# main_328p.net
KiCad netlist of a schematic drawn in EAGLE
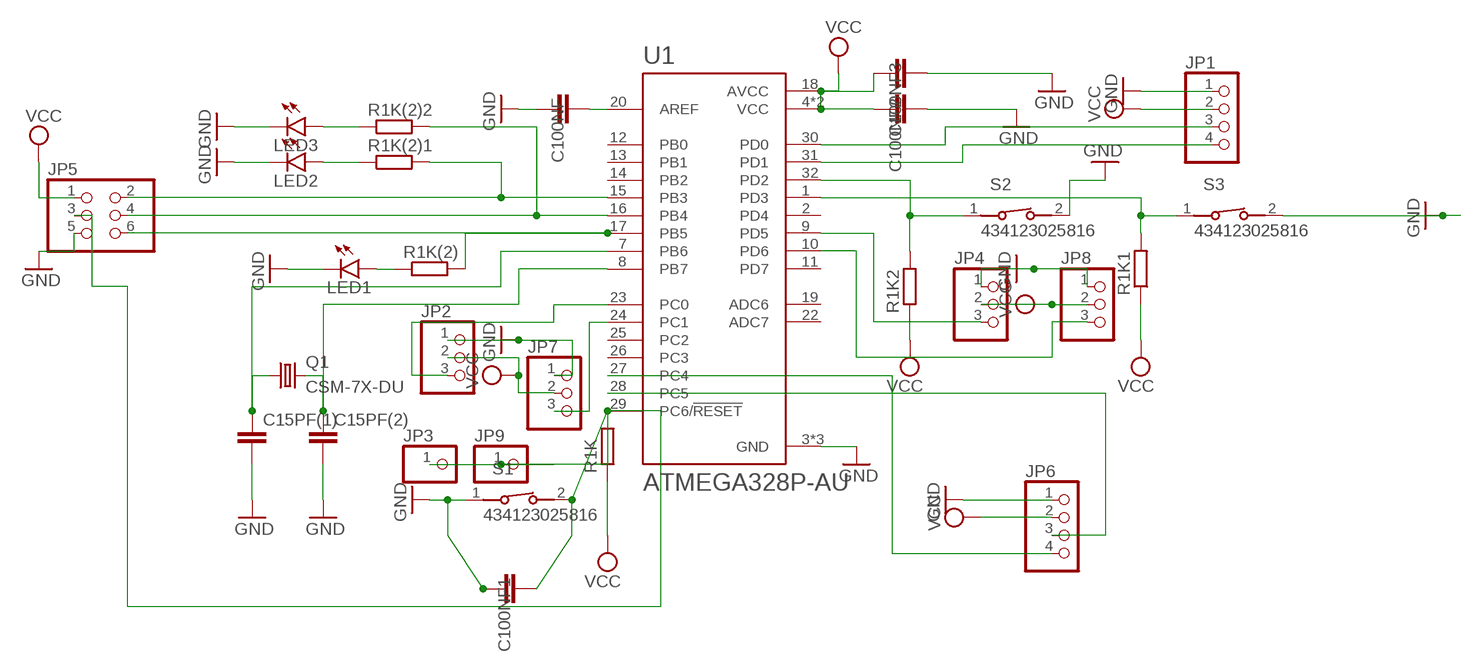
[diagram p0: schematic, sheet 1]

(export (version "E")
  (design (tool "Eeschema 10.0.6"))
  (components
    (comp (ref "C15PF(1)")
      (value "C-EUC0603")
      (footprint "eagle-import:C0603")
      (libsource (lib "eagle-import") (part "C-EUC0603"))
    )
    (comp (ref "C15PF(2)")
      (value "C-EUC0603")
      (footprint "eagle-import:C0603")
      (libsource (lib "eagle-import") (part "C-EUC0603"))
    )
    (comp (ref "C100NF")
      (value "C-EUC0603")
      (footprint "eagle-import:C0603")
      (libsource (lib "eagle-import") (part "C-EUC0603"))
    )
    (comp (ref "C100NF1")
      (value "C-EUC0603")
      (footprint "eagle-import:C0603")
      (libsource (lib "eagle-import") (part "C-EUC0603"))
    )
    (comp (ref "C100NF2")
      (value "C-EUC0603")
      (footprint "eagle-import:C0603")
      (libsource (lib "eagle-import") (part "C-EUC0603"))
    )
    (comp (ref "C100NF3")
      (value "C-EUC0603")
      (footprint "eagle-import:C0603")
      (libsource (lib "eagle-import") (part "C-EUC0603"))
    )
    (comp (ref "JP1")
      (value "PINHD-1X04_2.54-SMD")
      (footprint "eagle-import:1X04SMD")
      (libsource (lib "eagle-import") (part "PINHD-1X04_2.54-SMD"))
    )
    (comp (ref "JP2")
      (value "PINHD-1X03_2.54-SMD")
      (footprint "eagle-import:1X03SMD")
      (libsource (lib "eagle-import") (part "PINHD-1X03_2.54-SMD"))
    )
    (comp (ref "JP3")
      (value "PINHD-1X01_2.54")
      (footprint "eagle-import:1X01")
      (libsource (lib "eagle-import") (part "PINHD-1X01_2.54"))
    )
    (comp (ref "JP4")
      (value "PINHD-1X03_2.54-SMD")
      (footprint "eagle-import:1X03SMD")
      (libsource (lib "eagle-import") (part "PINHD-1X03_2.54-SMD"))
    )
    (comp (ref "JP5")
      (value "PINHD-2X03_2.54-SMD")
      (footprint "eagle-import:2X03SMD")
      (libsource (lib "eagle-import") (part "PINHD-2X03_2.54-SMD"))
    )
    (comp (ref "JP6")
      (value "PINHD-1X04_2.54-SMD")
      (footprint "eagle-import:1X04SMD")
      (libsource (lib "eagle-import") (part "PINHD-1X04_2.54-SMD"))
    )
    (comp (ref "JP7")
      (value "PINHD-1X03_2.54-SMD")
      (footprint "eagle-import:1X03SMD")
      (libsource (lib "eagle-import") (part "PINHD-1X03_2.54-SMD"))
    )
    (comp (ref "JP8")
      (value "PINHD-1X03_2.54-SMD")
      (footprint "eagle-import:1X03SMD")
      (libsource (lib "eagle-import") (part "PINHD-1X03_2.54-SMD"))
    )
    (comp (ref "JP9")
      (value "PINHD-1X01_2.54")
      (footprint "eagle-import:1X01")
      (libsource (lib "eagle-import") (part "PINHD-1X01_2.54"))
    )
    (comp (ref "LED1")
      (value "LEDCHIPLED_1206")
      (footprint "eagle-import:CHIPLED_1206")
      (libsource (lib "eagle-import") (part "LEDCHIPLED_1206"))
    )
    (comp (ref "LED2")
      (value "LEDCHIPLED_1206")
      (footprint "eagle-import:CHIPLED_1206")
      (libsource (lib "eagle-import") (part "LEDCHIPLED_1206"))
    )
    (comp (ref "LED3")
      (value "LEDCHIPLED_1206")
      (footprint "eagle-import:CHIPLED_1206")
      (libsource (lib "eagle-import") (part "LEDCHIPLED_1206"))
    )
    (comp (ref "Q1")
      (value "CSM-7X-DU")
      (footprint "eagle-import:CSM-7X-DU")
      (libsource (lib "eagle-import") (part "CSM-7X-DU"))
    )
    (comp (ref "R1K")
      (value "R-EU_R1206")
      (footprint "eagle-import:R1206")
      (libsource (lib "eagle-import") (part "R-EU_R1206"))
    )
    (comp (ref "R1K(2)")
      (value "R-EU_R1206")
      (footprint "eagle-import:R1206")
      (libsource (lib "eagle-import") (part "R-EU_R1206"))
    )
    (comp (ref "R1K(2)1")
      (value "R-EU_R1206")
      (footprint "eagle-import:R1206")
      (libsource (lib "eagle-import") (part "R-EU_R1206"))
    )
    (comp (ref "R1K(2)2")
      (value "R-EU_R1206")
      (footprint "eagle-import:R1206")
      (libsource (lib "eagle-import") (part "R-EU_R1206"))
    )
    (comp (ref "R1K1")
      (value "R-EU_R1206")
      (footprint "eagle-import:R1206")
      (libsource (lib "eagle-import") (part "R-EU_R1206"))
    )
    (comp (ref "R1K2")
      (value "R-EU_R1206")
      (footprint "eagle-import:R1206")
      (libsource (lib "eagle-import") (part "R-EU_R1206"))
    )
    (comp (ref "S1")
      (value "434123025816")
      (footprint "eagle-import:434123025816")
      (fields (field (name "MF") "Wurth Electronics"))
      (libsource (lib "eagle-import") (part "434123025816"))
    )
    (comp (ref "S2")
      (value "434123025816")
      (footprint "eagle-import:434123025816")
      (fields (field (name "MF") "Wurth Electronics"))
      (libsource (lib "eagle-import") (part "434123025816"))
    )
    (comp (ref "S3")
      (value "434123025816")
      (footprint "eagle-import:434123025816")
      (fields (field (name "MF") "Wurth Electronics"))
      (libsource (lib "eagle-import") (part "434123025816"))
    )
    (comp (ref "U1")
      (value "ATMEGA328P-AU")
      (footprint "eagle-import:QFP80P900X900X120-32N")
      (fields (field (name "MF") "Microchip Technology"))
      (libsource (lib "eagle-import") (part "ATMEGA328P-AU"))
    )
  )
  (nets
    (net (code "1") (name "GND") (class "Default")
      (node (ref "C100NF") (pin "1") (pinfunction "1_1") (pintype "passive"))
      (node (ref "C100NF1") (pin "1") (pinfunction "1_1") (pintype "passive"))
      (node (ref "C100NF2") (pin "2") (pinfunction "2_2") (pintype "passive"))
      (node (ref "C100NF3") (pin "2") (pinfunction "2_2") (pintype "passive"))
      (node (ref "C15PF(1)") (pin "2") (pinfunction "2_2") (pintype "passive"))
      (node (ref "C15PF(2)") (pin "2") (pinfunction "2_2") (pintype "passive"))
      (node (ref "JP1") (pin "1") (pinfunction "1_1") (pintype "passive"))
      (node (ref "JP2") (pin "1") (pinfunction "1_1") (pintype "passive"))
      (node (ref "JP4") (pin "1") (pinfunction "1_1") (pintype "passive"))
      (node (ref "JP5") (pin "5") (pinfunction "5_5") (pintype "passive"))
      (node (ref "JP6") (pin "1") (pinfunction "1_1") (pintype "passive"))
      (node (ref "JP7") (pin "1") (pinfunction "1_1") (pintype "passive"))
      (node (ref "JP8") (pin "1") (pinfunction "1_1") (pintype "passive"))
      (node (ref "LED1") (pin "C") (pinfunction "C_C") (pintype "passive"))
      (node (ref "LED2") (pin "C") (pinfunction "C_C") (pintype "passive"))
      (node (ref "LED3") (pin "C") (pinfunction "C_C") (pintype "passive"))
      (node (ref "S1") (pin "1") (pinfunction "1_1") (pintype "passive"))
      (node (ref "S2") (pin "2") (pinfunction "2_2") (pintype "passive"))
      (node (ref "S3") (pin "2") (pinfunction "2_2") (pintype "passive"))
      (node (ref "U1") (pin "21") (pinfunction "GND_21") (pintype "power_in"))
      (node (ref "U1") (pin "3") (pinfunction "GND_3") (pintype "power_in"))
      (node (ref "U1") (pin "5") (pinfunction "GND_5") (pintype "power_in"))
    )
    (net (code "2") (name "Net-(LED1-PadA)") (class "Default")
      (node (ref "LED1") (pin "A") (pinfunction "A_A") (pintype "passive"))
      (node (ref "R1K(2)") (pin "1") (pinfunction "1_1") (pintype "passive"))
    )
    (net (code "3") (name "Net-(LED2-PadA)") (class "Default")
      (node (ref "LED2") (pin "A") (pinfunction "A_A") (pintype "passive"))
      (node (ref "R1K(2)1") (pin "1") (pinfunction "1_1") (pintype "passive"))
    )
    (net (code "4") (name "Net-(LED3-PadA)") (class "Default")
      (node (ref "LED3") (pin "A") (pinfunction "A_A") (pintype "passive"))
      (node (ref "R1K(2)2") (pin "1") (pinfunction "1_1") (pintype "passive"))
    )
    (net (code "5") (name "Net-(U1-AREF)") (class "Default")
      (node (ref "C100NF") (pin "2") (pinfunction "2_2") (pintype "passive"))
      (node (ref "U1") (pin "20") (pinfunction "AREF_20") (pintype "input"))
    )
    (net (code "6") (name "Net-(U1-PB3)") (class "Default")
      (node (ref "JP5") (pin "2") (pinfunction "2_2") (pintype "passive"))
      (node (ref "R1K(2)1") (pin "2") (pinfunction "2_2") (pintype "passive"))
      (node (ref "U1") (pin "15") (pinfunction "PB3_15") (pintype "bidirectional"))
    )
    (net (code "7") (name "Net-(U1-PB4)") (class "Default")
      (node (ref "JP5") (pin "4") (pinfunction "4_4") (pintype "passive"))
      (node (ref "R1K(2)2") (pin "2") (pinfunction "2_2") (pintype "passive"))
      (node (ref "U1") (pin "16") (pinfunction "PB4_16") (pintype "bidirectional"))
    )
    (net (code "8") (name "Net-(U1-PB5)") (class "Default")
      (node (ref "JP5") (pin "6") (pinfunction "6_6") (pintype "passive"))
      (node (ref "R1K(2)") (pin "2") (pinfunction "2_2") (pintype "passive"))
      (node (ref "U1") (pin "17") (pinfunction "PB5_17") (pintype "bidirectional"))
    )
    (net (code "9") (name "Net-(U1-PB6)") (class "Default")
      (node (ref "C15PF(1)") (pin "1") (pinfunction "1_1") (pintype "passive"))
      (node (ref "Q1") (pin "1") (pinfunction "1_1") (pintype "passive"))
      (node (ref "U1") (pin "7") (pinfunction "PB6_7") (pintype "bidirectional"))
    )
    (net (code "10") (name "Net-(U1-PB7)") (class "Default")
      (node (ref "C15PF(2)") (pin "1") (pinfunction "1_1") (pintype "passive"))
      (node (ref "Q1") (pin "2") (pinfunction "2_2") (pintype "passive"))
      (node (ref "U1") (pin "8") (pinfunction "PB7_8") (pintype "bidirectional"))
    )
    (net (code "11") (name "Net-(U1-PC0)") (class "Default")
      (node (ref "JP2") (pin "3") (pinfunction "3_3") (pintype "passive"))
      (node (ref "U1") (pin "23") (pinfunction "PC0_23") (pintype "bidirectional"))
    )
    (net (code "12") (name "Net-(U1-PC1)") (class "Default")
      (node (ref "JP7") (pin "3") (pinfunction "3_3") (pintype "passive"))
      (node (ref "U1") (pin "24") (pinfunction "PC1_24") (pintype "bidirectional"))
    )
    (net (code "13") (name "Net-(U1-PC4)") (class "Default")
      (node (ref "JP6") (pin "4") (pinfunction "4_4") (pintype "passive"))
      (node (ref "U1") (pin "27") (pinfunction "PC4_27") (pintype "bidirectional"))
    )
    (net (code "14") (name "Net-(U1-PC5)") (class "Default")
      (node (ref "JP6") (pin "3") (pinfunction "3_3") (pintype "passive"))
      (node (ref "U1") (pin "28") (pinfunction "PC5_28") (pintype "bidirectional"))
    )
    (net (code "15") (name "Net-(U1-PC6{slash}~{RESET})") (class "Default")
      (node (ref "C100NF1") (pin "2") (pinfunction "2_2") (pintype "passive"))
      (node (ref "JP3") (pin "1") (pinfunction "1_1") (pintype "passive"))
      (node (ref "JP5") (pin "3") (pinfunction "3_3") (pintype "passive"))
      (node (ref "JP9") (pin "1") (pinfunction "1_1") (pintype "passive"))
      (node (ref "R1K") (pin "2") (pinfunction "2_2") (pintype "passive"))
      (node (ref "S1") (pin "2") (pinfunction "2_2") (pintype "passive"))
      (node (ref "U1") (pin "29") (pinfunction "PC6/~{RESET}_29") (pintype "bidirectional"))
    )
    (net (code "16") (name "Net-(U1-PD0)") (class "Default")
      (node (ref "JP1") (pin "3") (pinfunction "3_3") (pintype "passive"))
      (node (ref "U1") (pin "30") (pinfunction "PD0_30") (pintype "bidirectional"))
    )
    (net (code "17") (name "Net-(U1-PD1)") (class "Default")
      (node (ref "JP1") (pin "4") (pinfunction "4_4") (pintype "passive"))
      (node (ref "U1") (pin "31") (pinfunction "PD1_31") (pintype "bidirectional"))
    )
    (net (code "18") (name "Net-(U1-PD2)") (class "Default")
      (node (ref "R1K2") (pin "2") (pinfunction "2_2") (pintype "passive"))
      (node (ref "S2") (pin "1") (pinfunction "1_1") (pintype "passive"))
      (node (ref "U1") (pin "32") (pinfunction "PD2_32") (pintype "bidirectional"))
    )
    (net (code "19") (name "Net-(U1-PD3)") (class "Default")
      (node (ref "R1K1") (pin "2") (pinfunction "2_2") (pintype "passive"))
      (node (ref "S3") (pin "1") (pinfunction "1_1") (pintype "passive"))
      (node (ref "U1") (pin "1") (pinfunction "PD3_1") (pintype "bidirectional"))
    )
    (net (code "20") (name "Net-(U1-PD5)") (class "Default")
      (node (ref "JP4") (pin "3") (pinfunction "3_3") (pintype "passive"))
      (node (ref "U1") (pin "9") (pinfunction "PD5_9") (pintype "bidirectional"))
    )
    (net (code "21") (name "Net-(U1-PD6)") (class "Default")
      (node (ref "JP8") (pin "3") (pinfunction "3_3") (pintype "passive"))
      (node (ref "U1") (pin "10") (pinfunction "PD6_10") (pintype "bidirectional"))
    )
    (net (code "22") (name "VCC") (class "Default")
      (node (ref "C100NF2") (pin "1") (pinfunction "1_1") (pintype "passive"))
      (node (ref "C100NF3") (pin "1") (pinfunction "1_1") (pintype "passive"))
      (node (ref "JP1") (pin "2") (pinfunction "2_2") (pintype "passive"))
      (node (ref "JP2") (pin "2") (pinfunction "2_2") (pintype "passive"))
      (node (ref "JP4") (pin "2") (pinfunction "2_2") (pintype "passive"))
      (node (ref "JP5") (pin "1") (pinfunction "1_1") (pintype "passive"))
      (node (ref "JP6") (pin "2") (pinfunction "2_2") (pintype "passive"))
      (node (ref "JP7") (pin "2") (pinfunction "2_2") (pintype "passive"))
      (node (ref "JP8") (pin "2") (pinfunction "2_2") (pintype "passive"))
      (node (ref "R1K") (pin "1") (pinfunction "1_1") (pintype "passive"))
      (node (ref "R1K1") (pin "1") (pinfunction "1_1") (pintype "passive"))
      (node (ref "R1K2") (pin "1") (pinfunction "1_1") (pintype "passive"))
      (node (ref "U1") (pin "18") (pinfunction "AVCC_18") (pintype "power_in"))
      (node (ref "U1") (pin "4") (pinfunction "VCC_4") (pintype "power_in"))
      (node (ref "U1") (pin "6") (pinfunction "VCC_6") (pintype "power_in"))
    )
    (net (code "23") (name "unconnected-(U1-ADC6-Pad19)") (class "Default")
      (node (ref "U1") (pin "19") (pinfunction "ADC6_19") (pintype "bidirectional"))
    )
    (net (code "24") (name "unconnected-(U1-ADC7-Pad22)") (class "Default")
      (node (ref "U1") (pin "22") (pinfunction "ADC7_22") (pintype "bidirectional"))
    )
    (net (code "25") (name "unconnected-(U1-PB0-Pad12)") (class "Default")
      (node (ref "U1") (pin "12") (pinfunction "PB0_12") (pintype "bidirectional"))
    )
    (net (code "26") (name "unconnected-(U1-PB1-Pad13)") (class "Default")
      (node (ref "U1") (pin "13") (pinfunction "PB1_13") (pintype "bidirectional"))
    )
    (net (code "27") (name "unconnected-(U1-PB2-Pad14)") (class "Default")
      (node (ref "U1") (pin "14") (pinfunction "PB2_14") (pintype "bidirectional"))
    )
    (net (code "28") (name "unconnected-(U1-PC2-Pad25)") (class "Default")
      (node (ref "U1") (pin "25") (pinfunction "PC2_25") (pintype "bidirectional"))
    )
    (net (code "29") (name "unconnected-(U1-PC3-Pad26)") (class "Default")
      (node (ref "U1") (pin "26") (pinfunction "PC3_26") (pintype "bidirectional"))
    )
    (net (code "30") (name "unconnected-(U1-PD4-Pad2)") (class "Default")
      (node (ref "U1") (pin "2") (pinfunction "PD4_2") (pintype "bidirectional"))
    )
    (net (code "31") (name "unconnected-(U1-PD7-Pad11)") (class "Default")
      (node (ref "U1") (pin "11") (pinfunction "PD7_11") (pintype "bidirectional"))
    )
  )
)
